# LM2596.net
KiCad netlist of a schematic drawn in Altium Designer
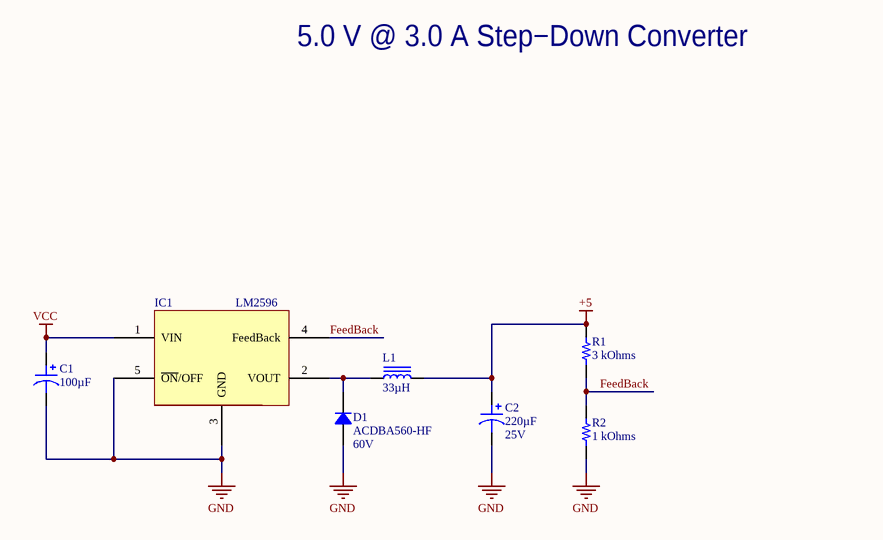
[diagram p0: LM2596.SchDoc]

(export (version "E")
  (design (tool "Eeschema 10.0.6"))
  (components
    (comp (ref "C1")
      (value "100µF")
      (footprint "CAP TH ALUM ELEC D8.00mm S3.50mm H12.50mm")
      (description "CAP ALUM 100UF 20% 50V RADIAL")
      (fields
        (field (name "PART NUMBER") "ECA-1HM101")
        (field (name "MANUFACTURER") "Panasonic Electronic Components")
      )
      (libsource (lib "Celestial Altium Library - altium_library") (part "Polarised Capacitor"))
    )
    (comp (ref "C2")
      (value "220µF")
      (footprint "CAP TH ALUM ELEC D6.30mm S2.50mm H12.50mm")
      (description "CAP ALUM 220UF 20% 25V RADIAL")
      (fields
        (field (name "PART NUMBER") "25YXJ220M6.3X11")
        (field (name "MANUFACTURER") "Rubycon")
        (field (name "VOLTAGE - RATED") "25V")
      )
      (libsource (lib "Celestial Altium Library - altium_library") (part "Polarised Capacitor"))
    )
    (comp (ref "D1")
      (value "ACDBA560-HF")
      (footprint "DO214AC SMA")
      (description "DIODE SCHOTTKY 60V 5A DO214AC")
      (fields
        (field (name "MANUFACTURER") "Comchip Technology")
        (field (name "VOLTAGE - DC REVERSE (VR) (MAX)") "60V")
      )
      (libsource (lib "Celestial Altium Library - altium_library") (part "Diode"))
    )
    (comp (ref "IC1") (value "LM2596") (footprint "LM2596") (libsource (lib "AltiumLive") (part "LM2596")))
    (comp (ref "L1")
      (value "33µH")
      (footprint "BOURNS SRR1280")
      (description "FIXED IND 33UH 3.5A 57 MOHM SMD")
      (fields (field (name "PART NUMBER") "SRR1280-330M") (field (name "MANUFACTURER") "Bourns Inc."))
      (libsource (lib "Celestial Altium Library - altium_library") (part "Inductor"))
    )
    (comp (ref "R1")
      (value "3 kOhms")
      (footprint "RES 0805_2012")
      (description "RES 3K OHM 5% 1/4W 0805")
      (fields
        (field (name "PART NUMBER") "RPC0805JT3K00")
        (field (name "MANUFACTURER") "Stackpole Electronics Inc")
      )
      (libsource (lib "Celestial Altium Library - altium_library") (part "Resistor"))
    )
    (comp (ref "R2")
      (value "1 kOhms")
      (footprint "RES 0805_2012")
      (description "RES 1K OHM 5% 1/4W 0805")
      (fields
        (field (name "PART NUMBER") "RPC0805JT1K00")
        (field (name "MANUFACTURER") "Stackpole Electronics Inc")
      )
      (libsource (lib "Celestial Altium Library - altium_library") (part "Resistor"))
    )
  )
  (nets
    (net (code "1") (name "+5") (class "Default")
      (node (ref "C2") (pin "1") (pinfunction "1_1") (pintype "passive"))
      (node (ref "L1") (pin "2") (pinfunction "2_2") (pintype "passive"))
      (node (ref "R1") (pin "2") (pinfunction "2_2") (pintype "passive"))
    )
    (net (code "2") (name "/FeedBack") (class "Default")
      (node (ref "IC1") (pin "4") (pinfunction "FeedBack_4") (pintype "passive"))
      (node (ref "R1") (pin "1") (pinfunction "1_1") (pintype "passive"))
      (node (ref "R2") (pin "2") (pinfunction "2_2") (pintype "passive"))
    )
    (net (code "3") (name "GND") (class "Default")
      (node (ref "C1") (pin "2") (pinfunction "2_2") (pintype "passive"))
      (node (ref "C2") (pin "2") (pinfunction "2_2") (pintype "passive"))
      (node (ref "D1") (pin "1") (pinfunction "1_1") (pintype "passive"))
      (node (ref "IC1") (pin "3") (pinfunction "GND_3") (pintype "passive"))
      (node (ref "IC1") (pin "5") (pinfunction "~{ON}/OFF_5") (pintype "passive"))
      (node (ref "R2") (pin "1") (pinfunction "1_1") (pintype "passive"))
    )
    (net (code "4") (name "Net-(IC1-VOUT)") (class "Default")
      (node (ref "D1") (pin "2") (pinfunction "2_2") (pintype "passive"))
      (node (ref "IC1") (pin "2") (pinfunction "VOUT_2") (pintype "passive"))
      (node (ref "L1") (pin "1") (pinfunction "1_1") (pintype "passive"))
    )
    (net (code "5") (name "VCC") (class "Default")
      (node (ref "C1") (pin "1") (pinfunction "1_1") (pintype "passive"))
      (node (ref "IC1") (pin "1") (pinfunction "VIN_1") (pintype "passive"))
    )
  )
)
